# TELEM_IF.net
KiCad netlist of a schematic drawn in Altium Designer
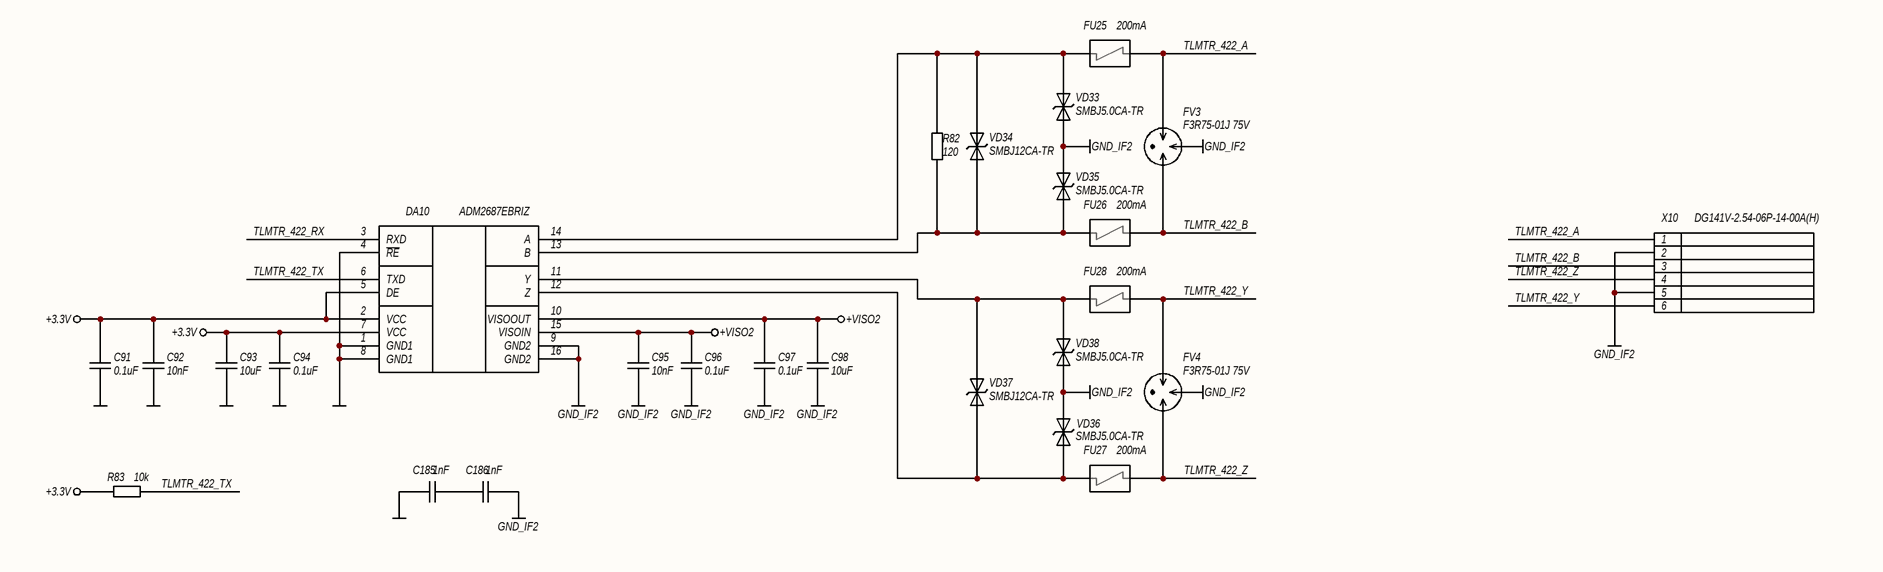
[diagram p0: TELEM_IF.SchDoc]

(export (version "E")
  (design (tool "Eeschema 10.0.6"))
  (components
    (comp (ref "C91")
      (value "0.1uF")
      (footprint "C0603N")
      (description "Конденсатор")
      (libsource (lib "Components Library") (part "CAP_FIXED"))
    )
    (comp (ref "C92")
      (value "10nF")
      (footprint "C0603N")
      (description "Конденсатор")
      (libsource (lib "Components Library") (part "CAP_FIXED"))
    )
    (comp (ref "C93")
      (value "10uF")
      (footprint "C0805N")
      (description "Конденсатор")
      (libsource (lib "Components Library") (part "CAP_FIXED"))
    )
    (comp (ref "C94")
      (value "0.1uF")
      (footprint "C0603N")
      (description "Конденсатор")
      (libsource (lib "Components Library") (part "CAP_FIXED"))
    )
    (comp (ref "C95")
      (value "10nF")
      (footprint "C0603N")
      (description "Конденсатор")
      (libsource (lib "Components Library") (part "CAP_FIXED"))
    )
    (comp (ref "C96")
      (value "0.1uF")
      (footprint "C0603N")
      (description "Конденсатор")
      (libsource (lib "Components Library") (part "CAP_FIXED"))
    )
    (comp (ref "C97")
      (value "0.1uF")
      (footprint "C0603N")
      (description "Конденсатор")
      (libsource (lib "Components Library") (part "CAP_FIXED"))
    )
    (comp (ref "C98")
      (value "10uF")
      (footprint "C0805N")
      (description "Конденсатор")
      (libsource (lib "Components Library") (part "CAP_FIXED"))
    )
    (comp (ref "C185")
      (value "1nF")
      (footprint "C1808N")
      (description "Конденсатор")
      (libsource (lib "Components Library") (part "CAP_FIXED"))
    )
    (comp (ref "C186")
      (value "1nF")
      (footprint "C1808N")
      (description "Конденсатор")
      (libsource (lib "Components Library") (part "CAP_FIXED"))
    )
    (comp (ref "DA10")
      (value "ADM2687EBRIZ")
      (footprint "SOIC16_IC")
      (description "Микросхема интерфейса RS485")
      (libsource (lib "Components Library") (part "ADM2687E"))
    )
    (comp (ref "FU25")
      (value "200mA")
      (footprint "TBU-CA")
      (description "Полупроводниковый предохранитель")
      (libsource (lib "Components Library") (part "FUSE_TBU"))
    )
    (comp (ref "FU26")
      (value "200mA")
      (footprint "TBU-CA")
      (description "Полупроводниковый предохранитель")
      (libsource (lib "Components Library") (part "FUSE_TBU"))
    )
    (comp (ref "FU27")
      (value "200mA")
      (footprint "TBU-CA")
      (description "Полупроводниковый предохранитель")
      (libsource (lib "Components Library") (part "FUSE_TBU"))
    )
    (comp (ref "FU28")
      (value "200mA")
      (footprint "TBU-CA")
      (description "Полупроводниковый предохранитель")
      (libsource (lib "Components Library") (part "FUSE_TBU"))
    )
    (comp (ref "FV3")
      (value "F3R75-01J 75V")
      (footprint "GDT_3PIN_B2")
      (description "Газовый разрядник, трехвыводный")
      (libsource (lib "Components Library") (part "GDT_3PIN"))
    )
    (comp (ref "FV4")
      (value "F3R75-01J 75V")
      (footprint "GDT_3PIN_B2")
      (description "Газовый разрядник, трехвыводный")
      (libsource (lib "Components Library") (part "GDT_3PIN"))
    )
    (comp (ref "R82")
      (value "120")
      (footprint "R0805N")
      (description "Резистор")
      (libsource (lib "") (part "RES_FIXED_1"))
    )
    (comp (ref "R83")
      (value "10k")
      (footprint "R0603N")
      (description "Резистор")
      (libsource (lib "Components Library") (part "RES_FIXED"))
    )
    (comp (ref "VD33")
      (value "SMBJ5.0CA-TR")
      (footprint "SMB")
      (description "TVS диод двунаправленный")
      (libsource (lib "Components Library") (part "TVS_BIDIR"))
    )
    (comp (ref "VD34")
      (value "SMBJ12CA-TR")
      (footprint "SMB")
      (description "TVS диод двунаправленный")
      (libsource (lib "Components Library") (part "TVS_BIDIR"))
    )
    (comp (ref "VD35")
      (value "SMBJ5.0CA-TR")
      (footprint "SMB")
      (description "TVS диод двунаправленный")
      (libsource (lib "Components Library") (part "TVS_BIDIR"))
    )
    (comp (ref "VD36")
      (value "SMBJ5.0CA-TR")
      (footprint "SMB")
      (description "TVS диод двунаправленный")
      (libsource (lib "Components Library") (part "TVS_BIDIR"))
    )
    (comp (ref "VD37")
      (value "SMBJ12CA-TR")
      (footprint "SMB")
      (description "TVS диод двунаправленный")
      (libsource (lib "Components Library") (part "TVS_BIDIR"))
    )
    (comp (ref "VD38")
      (value "SMBJ5.0CA-TR")
      (footprint "SMB")
      (description "TVS диод двунаправленный")
      (libsource (lib "Components Library") (part "TVS_BIDIR"))
    )
    (comp (ref "X10")
      (value "DG141V-2.54-06P-14-00A(H)")
      (footprint "DG141V-2.54-06P-14-00A(H)")
      (description "Разъем, 6 контактов")
      (libsource (lib "Components Library") (part "Connector 6"))
    )
  )
  (nets
    (net (code "1") (name "+3.3V") (class "Default")
      (node (ref "C91") (pin "2") (pinfunction "2_2") (pintype "passive"))
      (node (ref "C92") (pin "1") (pinfunction "1_1") (pintype "passive"))
      (node (ref "C93") (pin "2") (pinfunction "2_2") (pintype "passive"))
      (node (ref "C94") (pin "2") (pinfunction "2_2") (pintype "passive"))
      (node (ref "DA10") (pin "2") (pinfunction "VCC_2") (pintype "power_in"))
      (node (ref "DA10") (pin "5") (pinfunction "DE_5") (pintype "power_in"))
      (node (ref "DA10") (pin "7") (pinfunction "VCC_7") (pintype "power_in"))
      (node (ref "R83") (pin "2") (pinfunction "2_2") (pintype "passive"))
    )
    (net (code "2") (name "+VISO2") (class "Default")
      (node (ref "C95") (pin "1") (pinfunction "1_1") (pintype "passive"))
      (node (ref "C96") (pin "2") (pinfunction "2_2") (pintype "passive"))
      (node (ref "C97") (pin "2") (pinfunction "2_2") (pintype "passive"))
      (node (ref "C98") (pin "2") (pinfunction "2_2") (pintype "passive"))
      (node (ref "DA10") (pin "10") (pinfunction "VISOOUT_10") (pintype "power_in"))
      (node (ref "DA10") (pin "15") (pinfunction "VISOIN_15") (pintype "power_in"))
    )
    (net (code "3") (name "/TLMTR_422_A") (class "Default")
      (node (ref "FU25") (pin "3") (pinfunction "IN/OUT_3") (pintype "passive"))
      (node (ref "FV3") (pin "1") (pinfunction "1_1") (pintype "passive"))
      (node (ref "X10") (pin "1") (pinfunction "1_1") (pintype "power_in"))
    )
    (net (code "4") (name "/TLMTR_422_B") (class "Default")
      (node (ref "FU26") (pin "3") (pinfunction "IN/OUT_3") (pintype "passive"))
      (node (ref "FV3") (pin "3") (pinfunction "3_3") (pintype "passive"))
      (node (ref "X10") (pin "3") (pinfunction "3_3") (pintype "power_in"))
    )
    (net (code "5") (name "/TLMTR_422_RX") (class "Default")
      (node (ref "DA10") (pin "3") (pinfunction "RXD_3") (pintype "power_in"))
    )
    (net (code "6") (name "/TLMTR_422_TX") (class "Default")
      (node (ref "DA10") (pin "6") (pinfunction "TXD_6") (pintype "power_in"))
      (node (ref "R83") (pin "1") (pinfunction "1_1") (pintype "passive"))
    )
    (net (code "7") (name "/TLMTR_422_Y") (class "Default")
      (node (ref "FU28") (pin "3") (pinfunction "IN/OUT_3") (pintype "passive"))
      (node (ref "FV4") (pin "3") (pinfunction "3_3") (pintype "passive"))
      (node (ref "X10") (pin "6") (pinfunction "6_6") (pintype "power_in"))
    )
    (net (code "8") (name "/TLMTR_422_Z") (class "Default")
      (node (ref "FU27") (pin "3") (pinfunction "IN/OUT_3") (pintype "passive"))
      (node (ref "FV4") (pin "1") (pinfunction "1_1") (pintype "passive"))
      (node (ref "X10") (pin "4") (pinfunction "4_4") (pintype "power_in"))
    )
    (net (code "9") (name "GND") (class "Default")
      (node (ref "C185") (pin "2") (pinfunction "2_2") (pintype "passive"))
      (node (ref "C91") (pin "1") (pinfunction "1_1") (pintype "passive"))
      (node (ref "C92") (pin "2") (pinfunction "2_2") (pintype "passive"))
      (node (ref "C93") (pin "1") (pinfunction "1_1") (pintype "passive"))
      (node (ref "C94") (pin "1") (pinfunction "1_1") (pintype "passive"))
      (node (ref "DA10") (pin "1") (pinfunction "GND1_1") (pintype "power_in"))
      (node (ref "DA10") (pin "4") (pinfunction "~{RE}_4") (pintype "power_in"))
      (node (ref "DA10") (pin "8") (pinfunction "GND1_8") (pintype "power_in"))
    )
    (net (code "10") (name "GND_IF2") (class "Default")
      (node (ref "C186") (pin "1") (pinfunction "1_1") (pintype "passive"))
      (node (ref "C95") (pin "2") (pinfunction "2_2") (pintype "passive"))
      (node (ref "C96") (pin "1") (pinfunction "1_1") (pintype "passive"))
      (node (ref "C97") (pin "1") (pinfunction "1_1") (pintype "passive"))
      (node (ref "C98") (pin "1") (pinfunction "1_1") (pintype "passive"))
      (node (ref "DA10") (pin "16") (pinfunction "GND2_16") (pintype "power_in"))
      (node (ref "DA10") (pin "9") (pinfunction "GND2_9") (pintype "power_in"))
      (node (ref "FV3") (pin "2") (pinfunction "2_2") (pintype "passive"))
      (node (ref "FV4") (pin "2") (pinfunction "2_2") (pintype "passive"))
      (node (ref "VD33") (pin "2") (pinfunction "A2_2") (pintype "passive"))
      (node (ref "VD35") (pin "2") (pinfunction "A2_2") (pintype "passive"))
      (node (ref "VD36") (pin "2") (pinfunction "A2_2") (pintype "passive"))
      (node (ref "VD38") (pin "2") (pinfunction "A2_2") (pintype "passive"))
      (node (ref "X10") (pin "2") (pinfunction "2_2") (pintype "power_in"))
      (node (ref "X10") (pin "5") (pinfunction "5_5") (pintype "power_in"))
    )
    (net (code "11") (name "Net-(C185-Pad1)") (class "Default")
      (node (ref "C185") (pin "1") (pinfunction "1_1") (pintype "passive"))
      (node (ref "C186") (pin "2") (pinfunction "2_2") (pintype "passive"))
    )
    (net (code "12") (name "Net-(DA10-A)") (class "Default")
      (node (ref "DA10") (pin "14") (pinfunction "A_14") (pintype "power_in"))
      (node (ref "FU25") (pin "1") (pinfunction "IN/OUT_1") (pintype "passive"))
      (node (ref "R82") (pin "1") (pinfunction "1_1") (pintype "passive"))
      (node (ref "VD33") (pin "1") (pinfunction "A1_1") (pintype "passive"))
      (node (ref "VD34") (pin "1") (pinfunction "A1_1") (pintype "passive"))
    )
    (net (code "13") (name "Net-(DA10-B)") (class "Default")
      (node (ref "DA10") (pin "13") (pinfunction "B_13") (pintype "power_in"))
      (node (ref "FU26") (pin "1") (pinfunction "IN/OUT_1") (pintype "passive"))
      (node (ref "R82") (pin "2") (pinfunction "2_2") (pintype "passive"))
      (node (ref "VD34") (pin "2") (pinfunction "A2_2") (pintype "passive"))
      (node (ref "VD35") (pin "1") (pinfunction "A1_1") (pintype "passive"))
    )
    (net (code "14") (name "Net-(DA10-Y)") (class "Default")
      (node (ref "DA10") (pin "11") (pinfunction "Y_11") (pintype "power_in"))
      (node (ref "FU28") (pin "1") (pinfunction "IN/OUT_1") (pintype "passive"))
      (node (ref "VD37") (pin "2") (pinfunction "A2_2") (pintype "passive"))
      (node (ref "VD38") (pin "1") (pinfunction "A1_1") (pintype "passive"))
    )
    (net (code "15") (name "Net-(DA10-Z)") (class "Default")
      (node (ref "DA10") (pin "12") (pinfunction "Z_12") (pintype "power_in"))
      (node (ref "FU27") (pin "1") (pinfunction "IN/OUT_1") (pintype "passive"))
      (node (ref "VD36") (pin "1") (pinfunction "A1_1") (pintype "passive"))
      (node (ref "VD37") (pin "1") (pinfunction "A1_1") (pintype "passive"))
    )
  )
)
